# what-the-frequency-mk-4.net
KiCad netlist of a schematic drawn in EAGLE
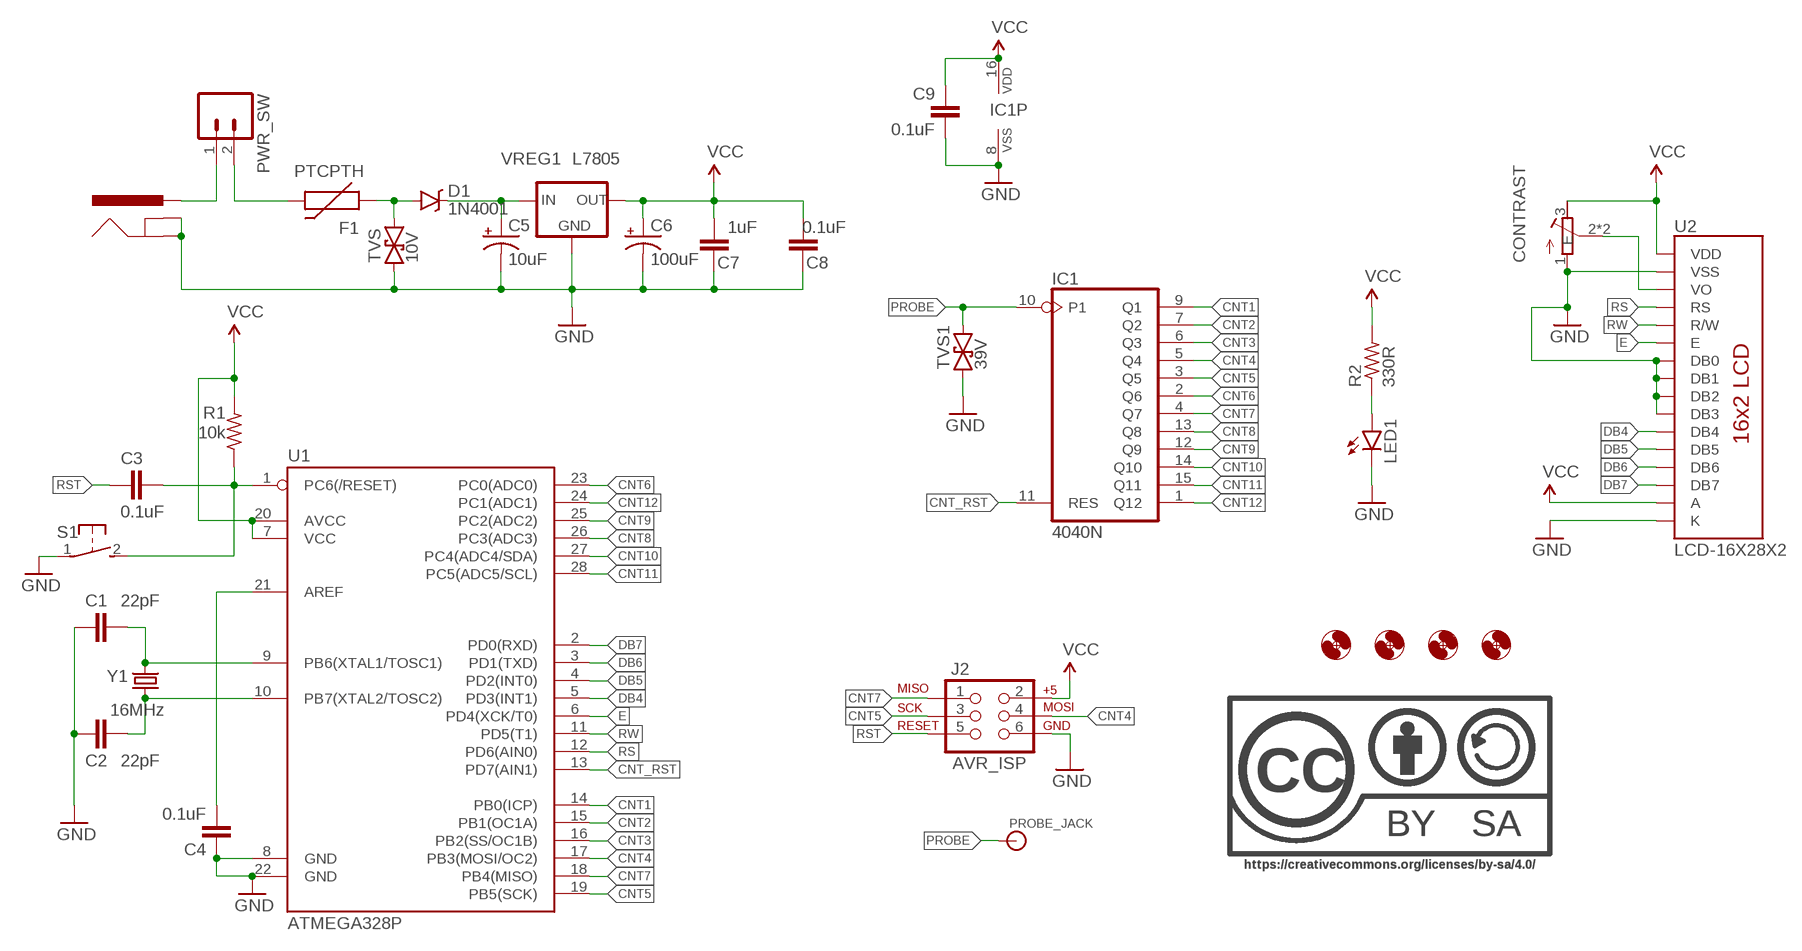
[diagram p0: schematic, sheet 1]

(export (version "E")
  (design (tool "Eeschema 10.0.6"))
  (components
    (comp (ref "C1")
      (value "22pF")
      (footprint "eagle-import:C025-024X044")
      (libsource (lib "eagle-import") (part "CAPACITOR-CERAMIC025-024X044"))
    )
    (comp (ref "C2")
      (value "22pF")
      (footprint "eagle-import:C025-024X044")
      (libsource (lib "eagle-import") (part "CAPACITOR-CERAMIC025-024X044"))
    )
    (comp (ref "C3")
      (value "0.1uF")
      (footprint "eagle-import:C025-024X044")
      (libsource (lib "eagle-import") (part "CAPACITOR-CERAMIC025-024X044"))
    )
    (comp (ref "C4")
      (value "0.1uF")
      (footprint "eagle-import:C025-024X044")
      (libsource (lib "eagle-import") (part "CAPACITOR-CERAMIC025-024X044"))
    )
    (comp (ref "C5")
      (value "10uF")
      (footprint "eagle-import:E2-5")
      (libsource (lib "eagle-import") (part "CAPACITOR-POLARIZEDE2-5"))
    )
    (comp (ref "C6")
      (value "100uF")
      (footprint "eagle-import:E2,5-6")
      (libsource (lib "eagle-import") (part "CAPACITOR-POLARIZEDE2.5-6"))
    )
    (comp (ref "C7")
      (value "1uF")
      (footprint "eagle-import:C025-024X044")
      (libsource (lib "eagle-import") (part "CAPACITOR-CERAMIC025-024X044"))
    )
    (comp (ref "C8")
      (value "0.1uF")
      (footprint "eagle-import:C025-024X044")
      (libsource (lib "eagle-import") (part "CAPACITOR-CERAMIC025-024X044"))
    )
    (comp (ref "C9")
      (value "0.1uF")
      (footprint "eagle-import:C025-024X044")
      (libsource (lib "eagle-import") (part "CAPACITOR-CERAMIC025-024X044"))
    )
    (comp (ref "CONTRAST")
      (value "POTENTIOMETERTHUMBWHEEL-16MM")
      (footprint "eagle-import:POT-THUMBWHEEL")
      (libsource (lib "eagle-import") (part "POTENTIOMETERTHUMBWHEEL-16MM"))
    )
    (comp (ref "D1")
      (value "1N4001")
      (footprint "eagle-import:DO-41")
      (libsource (lib "eagle-import") (part "DIODE-SCHOTTKYDO-41"))
    )
    (comp (ref "F1")
      (value "PTCPTH")
      (footprint "eagle-import:PTC")
      (libsource (lib "eagle-import") (part "PTCPTH"))
    )
    (comp (ref "H1")
      (value "HOLE#4")
      (footprint "eagle-import:HOLE-#4")
      (libsource (lib "eagle-import") (part "HOLE#4"))
    )
    (comp (ref "H2")
      (value "HOLE#4")
      (footprint "eagle-import:HOLE-#4")
      (libsource (lib "eagle-import") (part "HOLE#4"))
    )
    (comp (ref "H3")
      (value "HOLE#4")
      (footprint "eagle-import:HOLE-#4")
      (libsource (lib "eagle-import") (part "HOLE#4"))
    )
    (comp (ref "H4")
      (value "HOLE#4")
      (footprint "eagle-import:HOLE-#4")
      (libsource (lib "eagle-import") (part "HOLE#4"))
    )
    (comp (ref "IC1")
      (value "4040N")
      (footprint "eagle-import:DIL16")
      (libsource (lib "eagle-import") (part "4040N"))
    )
    (comp (ref "J1")
      (value "POWER_JACKPTH")
      (footprint "eagle-import:POWER_JACK_PTH")
      (libsource (lib "eagle-import") (part "POWER_JACKPTH"))
    )
    (comp (ref "J2")
      (value "AVR_ISP")
      (footprint "eagle-import:AVR_MINI_PROG")
      (libsource (lib "eagle-import") (part "AVR_SPI_PRG_6INLINE"))
    )
    (comp (ref "LED1")
      (value "LED3MM")
      (footprint "eagle-import:LED3MM")
      (libsource (lib "eagle-import") (part "LED3MM"))
    )
    (comp (ref "PROBE_JACK")
      (value "BANANA_CONNPTH-RA")
      (footprint "eagle-import:BANANA-PTH-RA-SAFEWORD")
      (libsource (lib "eagle-import") (part "BANANA_CONNPTH-RA"))
    )
    (comp (ref "PWR_SW")
      (value "M02PTH")
      (footprint "eagle-import:1X02")
      (libsource (lib "eagle-import") (part "M02PTH"))
    )
    (comp (ref "R1")
      (value "10k")
      (footprint "eagle-import:RESISTOR-AXIAL-PTH-7.68MM")
      (libsource (lib "eagle-import") (part "RESISTORAXIAL-PTH-7.68MM"))
    )
    (comp (ref "R2")
      (value "330R")
      (footprint "eagle-import:RESISTOR-AXIAL-PTH-5.08MM")
      (libsource (lib "eagle-import") (part "RESISTORPTH-AXIAL-5.08MM"))
    )
    (comp (ref "S1")
      (value "DTS-3")
      (footprint "eagle-import:DTS-3")
      (libsource (lib "eagle-import") (part "DTS-3"))
    )
    (comp (ref "TVS")
      (value "10V")
      (footprint "eagle-import:DO-41-TVS")
      (libsource (lib "eagle-import") (part "TVSDO-41-TVS-BIDIRECTIONAL"))
    )
    (comp (ref "TVS1")
      (value "39V")
      (footprint "eagle-import:DO-41-TVS")
      (libsource (lib "eagle-import") (part "TVSDO-41-TVS-BIDIRECTIONAL"))
    )
    (comp (ref "U$3")
      (value "CC-BY-SA-4.0URL-BOTTOM")
      (footprint "eagle-import:CC-BY-SA-4.0-URL-BOTTOM")
      (libsource (lib "eagle-import") (part "CC-BY-SA-4.0URL-BOTTOM"))
    )
    (comp (ref "U$7")
      (value "CC-BY-SA-4.0NO-URL")
      (footprint "eagle-import:CC-BY-SA-4.0-NO-URL")
      (libsource (lib "eagle-import") (part "CC-BY-SA-4.0NO-URL"))
    )
    (comp (ref "U1")
      (value "ATMEGA328P")
      (footprint "eagle-import:DIL28-3")
      (libsource (lib "eagle-import") (part "ATMEGA328P_PDIP"))
    )
    (comp (ref "U2")
      (value "LCD-16X28X2")
      (footprint "eagle-import:LCD-8X2")
      (libsource (lib "eagle-import") (part "LCD-16X28X2"))
    )
    (comp (ref "VREG1")
      (value "L7805")
      (footprint "eagle-import:TO-92-AMMO")
      (libsource (lib "eagle-import") (part "V_REG_78XXTO-92-INLINE"))
    )
    (comp (ref "Y1")
      (value "16MHz")
      (footprint "eagle-import:HC49U-V")
      (libsource (lib "eagle-import") (part "CRYSTALHC49UV"))
    )
  )
  (nets
    (net (code "1") (name "CNT1") (class "Default")
      (node (ref "IC1") (pin "9") (pinfunction "Q1_9") (pintype "output"))
      (node (ref "U1") (pin "14") (pinfunction "PB0(ICP)_14") (pintype "bidirectional"))
    )
    (net (code "2") (name "CNT2") (class "Default")
      (node (ref "IC1") (pin "7") (pinfunction "Q2_7") (pintype "output"))
      (node (ref "U1") (pin "15") (pinfunction "PB1(OC1A)_15") (pintype "bidirectional"))
    )
    (net (code "3") (name "CNT3") (class "Default")
      (node (ref "IC1") (pin "6") (pinfunction "Q3_6") (pintype "output"))
      (node (ref "U1") (pin "16") (pinfunction "PB2(SS/OC1B)_16") (pintype "bidirectional"))
    )
    (net (code "4") (name "CNT4") (class "Default")
      (node (ref "IC1") (pin "5") (pinfunction "Q4_5") (pintype "output"))
      (node (ref "J2") (pin "4") (pinfunction "4_4") (pintype "passive"))
      (node (ref "U1") (pin "17") (pinfunction "PB3(MOSI/OC2)_17") (pintype "bidirectional"))
    )
    (net (code "5") (name "CNT5") (class "Default")
      (node (ref "IC1") (pin "3") (pinfunction "Q5_3") (pintype "output"))
      (node (ref "J2") (pin "3") (pinfunction "3_3") (pintype "passive"))
      (node (ref "U1") (pin "19") (pinfunction "PB5(SCK)_19") (pintype "bidirectional"))
    )
    (net (code "6") (name "CNT6") (class "Default")
      (node (ref "IC1") (pin "2") (pinfunction "Q6_2") (pintype "output"))
      (node (ref "U1") (pin "23") (pinfunction "PC0(ADC0)_23") (pintype "bidirectional"))
    )
    (net (code "7") (name "CNT7") (class "Default")
      (node (ref "IC1") (pin "4") (pinfunction "Q7_4") (pintype "output"))
      (node (ref "J2") (pin "1") (pinfunction "1_1") (pintype "passive"))
      (node (ref "U1") (pin "18") (pinfunction "PB4(MISO)_18") (pintype "bidirectional"))
    )
    (net (code "8") (name "CNT8") (class "Default")
      (node (ref "IC1") (pin "13") (pinfunction "Q8_13") (pintype "output"))
      (node (ref "U1") (pin "26") (pinfunction "PC3(ADC3)_26") (pintype "bidirectional"))
    )
    (net (code "9") (name "CNT9") (class "Default")
      (node (ref "IC1") (pin "12") (pinfunction "Q9_12") (pintype "output"))
      (node (ref "U1") (pin "25") (pinfunction "PC2(ADC2)_25") (pintype "bidirectional"))
    )
    (net (code "10") (name "CNT10") (class "Default")
      (node (ref "IC1") (pin "14") (pinfunction "Q10_14") (pintype "output"))
      (node (ref "U1") (pin "27") (pinfunction "PC4(ADC4/SDA)_27") (pintype "bidirectional"))
    )
    (net (code "11") (name "CNT11") (class "Default")
      (node (ref "IC1") (pin "15") (pinfunction "Q11_15") (pintype "output"))
      (node (ref "U1") (pin "28") (pinfunction "PC5(ADC5/SCL)_28") (pintype "bidirectional"))
    )
    (net (code "12") (name "CNT12") (class "Default")
      (node (ref "IC1") (pin "1") (pinfunction "Q12_1") (pintype "output"))
      (node (ref "U1") (pin "24") (pinfunction "PC1(ADC1)_24") (pintype "bidirectional"))
    )
    (net (code "13") (name "CNT_RST") (class "Default")
      (node (ref "IC1") (pin "11") (pinfunction "RES_11") (pintype "input"))
      (node (ref "U1") (pin "13") (pinfunction "PD7(AIN1)_13") (pintype "bidirectional"))
    )
    (net (code "14") (name "DB4") (class "Default")
      (node (ref "U1") (pin "5") (pinfunction "PD3(INT1)_5") (pintype "bidirectional"))
      (node (ref "U2") (pin "11") (pinfunction "DB4_11") (pintype "bidirectional"))
    )
    (net (code "15") (name "DB5") (class "Default")
      (node (ref "U1") (pin "4") (pinfunction "PD2(INT0)_4") (pintype "bidirectional"))
      (node (ref "U2") (pin "12") (pinfunction "DB5_12") (pintype "bidirectional"))
    )
    (net (code "16") (name "DB6") (class "Default")
      (node (ref "U1") (pin "3") (pinfunction "PD1(TXD)_3") (pintype "bidirectional"))
      (node (ref "U2") (pin "13") (pinfunction "DB6_13") (pintype "bidirectional"))
    )
    (net (code "17") (name "DB7") (class "Default")
      (node (ref "U1") (pin "2") (pinfunction "PD0(RXD)_2") (pintype "bidirectional"))
      (node (ref "U2") (pin "14") (pinfunction "DB7_14") (pintype "bidirectional"))
    )
    (net (code "18") (name "E") (class "Default")
      (node (ref "U1") (pin "6") (pinfunction "PD4(XCK/T0)_6") (pintype "bidirectional"))
      (node (ref "U2") (pin "6") (pinfunction "E_6") (pintype "input"))
    )
    (net (code "19") (name "GND") (class "Default")
      (node (ref "C1") (pin "2") (pinfunction "2_2") (pintype "passive"))
      (node (ref "C2") (pin "2") (pinfunction "2_2") (pintype "passive"))
      (node (ref "C4") (pin "1") (pinfunction "1_1") (pintype "passive"))
      (node (ref "C5") (pin "-") (pinfunction "-_-") (pintype "passive"))
      (node (ref "C6") (pin "-") (pinfunction "-_-") (pintype "passive"))
      (node (ref "C7") (pin "1") (pinfunction "1_1") (pintype "passive"))
      (node (ref "C8") (pin "1") (pinfunction "1_1") (pintype "passive"))
      (node (ref "C9") (pin "1") (pinfunction "1_1") (pintype "passive"))
      (node (ref "CONTRAST") (pin "1") (pinfunction "A_1") (pintype "passive"))
      (node (ref "IC1") (pin "8") (pinfunction "VSS_8") (pintype "power_in"))
      (node (ref "J1") (pin "GND") (pinfunction "GND_GND") (pintype "bidirectional"))
      (node (ref "J1") (pin "GNDBREAK") (pinfunction "GNDBREAK_GNDBREAK") (pintype "bidirectional"))
      (node (ref "J2") (pin "6") (pinfunction "6_6") (pintype "passive"))
      (node (ref "LED1") (pin "K") (pinfunction "C_K") (pintype "passive"))
      (node (ref "S1") (pin "1") (pinfunction "1_1") (pintype "passive"))
      (node (ref "TVS") (pin "P$1") (pinfunction "1_P$1") (pintype "passive"))
      (node (ref "TVS1") (pin "P$1") (pinfunction "1_P$1") (pintype "passive"))
      (node (ref "U1") (pin "22") (pinfunction "GND_22") (pintype "bidirectional"))
      (node (ref "U1") (pin "8") (pinfunction "GND_8") (pintype "bidirectional"))
      (node (ref "U2") (pin "1") (pinfunction "VSS_1") (pintype "power_in"))
      (node (ref "U2") (pin "10") (pinfunction "DB3_10") (pintype "bidirectional"))
      (node (ref "U2") (pin "16") (pinfunction "K_16") (pintype "power_in"))
      (node (ref "U2") (pin "7") (pinfunction "DB0_7") (pintype "bidirectional"))
      (node (ref "U2") (pin "8") (pinfunction "DB1_8") (pintype "bidirectional"))
      (node (ref "U2") (pin "9") (pinfunction "DB2_9") (pintype "bidirectional"))
      (node (ref "VREG1") (pin "2") (pinfunction "GND_2") (pintype "input"))
    )
    (net (code "20") (name "Net-(F1-1)") (class "Default")
      (node (ref "D1") (pin "A") (pinfunction "A_A") (pintype "passive"))
      (node (ref "F1") (pin "P$1") (pinfunction "1_P$1") (pintype "bidirectional"))
      (node (ref "TVS") (pin "P$2") (pinfunction "2_P$2") (pintype "passive"))
    )
    (net (code "21") (name "Net-(F1-2)") (class "Default")
      (node (ref "F1") (pin "P$2") (pinfunction "2_P$2") (pintype "bidirectional"))
      (node (ref "PWR_SW") (pin "2") (pinfunction "2_2") (pintype "passive"))
    )
    (net (code "22") (name "Net-(J1-PadPWR)") (class "Default")
      (node (ref "J1") (pin "PWR") (pinfunction "PWR_PWR") (pintype "bidirectional"))
      (node (ref "PWR_SW") (pin "1") (pinfunction "1_1") (pintype "passive"))
    )
    (net (code "23") (name "Net-(R1-1)") (class "Default")
      (node (ref "C3") (pin "2") (pinfunction "2_2") (pintype "passive"))
      (node (ref "R1") (pin "P$1") (pinfunction "1_P$1") (pintype "passive"))
      (node (ref "S1") (pin "2") (pinfunction "2_2") (pintype "passive"))
      (node (ref "U1") (pin "1") (pinfunction "PC6(/RESET)_1") (pintype "bidirectional"))
    )
    (net (code "24") (name "Net-(R2-1)") (class "Default")
      (node (ref "LED1") (pin "A") (pinfunction "A_A") (pintype "passive"))
      (node (ref "R2") (pin "P$1") (pinfunction "1_P$1") (pintype "passive"))
    )
    (net (code "25") (name "Net-(U1-AREF)") (class "Default")
      (node (ref "C4") (pin "2") (pinfunction "2_2") (pintype "passive"))
      (node (ref "U1") (pin "21") (pinfunction "AREF_21") (pintype "bidirectional"))
    )
    (net (code "26") (name "Net-(U1-PB6(XTAL1{slash}TOSC1))") (class "Default")
      (node (ref "C1") (pin "1") (pinfunction "1_1") (pintype "passive"))
      (node (ref "U1") (pin "9") (pinfunction "PB6(XTAL1/TOSC1)_9") (pintype "bidirectional"))
      (node (ref "Y1") (pin "2") (pinfunction "2_2") (pintype "passive"))
    )
    (net (code "27") (name "Net-(U1-PB7(XTAL2{slash}TOSC2))") (class "Default")
      (node (ref "C2") (pin "1") (pinfunction "1_1") (pintype "passive"))
      (node (ref "U1") (pin "10") (pinfunction "PB7(XTAL2/TOSC2)_10") (pintype "bidirectional"))
      (node (ref "Y1") (pin "1") (pinfunction "1_1") (pintype "passive"))
    )
    (net (code "28") (name "Net-(U2-VO)") (class "Default")
      (node (ref "CONTRAST") (pin "2") (pinfunction "S_2") (pintype "passive"))
      (node (ref "CONTRAST") (pin "2@1") (pinfunction "S_2@1") (pintype "passive"))
      (node (ref "U2") (pin "3") (pinfunction "VO_3") (pintype "bidirectional"))
    )
    (net (code "29") (name "Net-(VREG1-IN)") (class "Default")
      (node (ref "C5") (pin "+") (pinfunction "+_+") (pintype "passive"))
      (node (ref "D1") (pin "C") (pinfunction "C_C") (pintype "passive"))
      (node (ref "VREG1") (pin "1") (pinfunction "IN_1") (pintype "input"))
    )
    (net (code "30") (name "PROBE") (class "Default")
      (node (ref "IC1") (pin "10") (pinfunction "P1_10") (pintype "input"))
      (node (ref "PROBE_JACK") (pin "P$1") (pinfunction "1_P$1") (pintype "passive"))
      (node (ref "PROBE_JACK") (pin "P$2") (pinfunction "1_P$2") (pintype "passive"))
      (node (ref "TVS1") (pin "P$2") (pinfunction "2_P$2") (pintype "passive"))
    )
    (net (code "31") (name "RS") (class "Default")
      (node (ref "U1") (pin "12") (pinfunction "PD6(AIN0)_12") (pintype "bidirectional"))
      (node (ref "U2") (pin "4") (pinfunction "RS_4") (pintype "input"))
    )
    (net (code "32") (name "RST") (class "Default")
      (node (ref "C3") (pin "1") (pinfunction "1_1") (pintype "passive"))
      (node (ref "J2") (pin "5") (pinfunction "5_5") (pintype "passive"))
    )
    (net (code "33") (name "RW") (class "Default")
      (node (ref "U1") (pin "11") (pinfunction "PD5(T1)_11") (pintype "bidirectional"))
      (node (ref "U2") (pin "5") (pinfunction "R/W_5") (pintype "input"))
    )
    (net (code "34") (name "VCC") (class "Default")
      (node (ref "C6") (pin "+") (pinfunction "+_+") (pintype "passive"))
      (node (ref "C7") (pin "2") (pinfunction "2_2") (pintype "passive"))
      (node (ref "C8") (pin "2") (pinfunction "2_2") (pintype "passive"))
      (node (ref "C9") (pin "2") (pinfunction "2_2") (pintype "passive"))
      (node (ref "CONTRAST") (pin "3") (pinfunction "E_3") (pintype "passive"))
      (node (ref "IC1") (pin "16") (pinfunction "VDD_16") (pintype "power_in"))
      (node (ref "J2") (pin "2") (pinfunction "2_2") (pintype "passive"))
      (node (ref "R1") (pin "P$2") (pinfunction "2_P$2") (pintype "passive"))
      (node (ref "R2") (pin "P$2") (pinfunction "2_P$2") (pintype "passive"))
      (node (ref "U1") (pin "20") (pinfunction "AVCC_20") (pintype "bidirectional"))
      (node (ref "U1") (pin "7") (pinfunction "VCC_7") (pintype "bidirectional"))
      (node (ref "U2") (pin "15") (pinfunction "A_15") (pintype "power_in"))
      (node (ref "U2") (pin "2") (pinfunction "VDD_2") (pintype "power_in"))
      (node (ref "VREG1") (pin "3") (pinfunction "OUT_3") (pintype "output"))
    )
  )
)
